# Pi-LPF.net
KiCad netlist of a schematic drawn in EAGLE
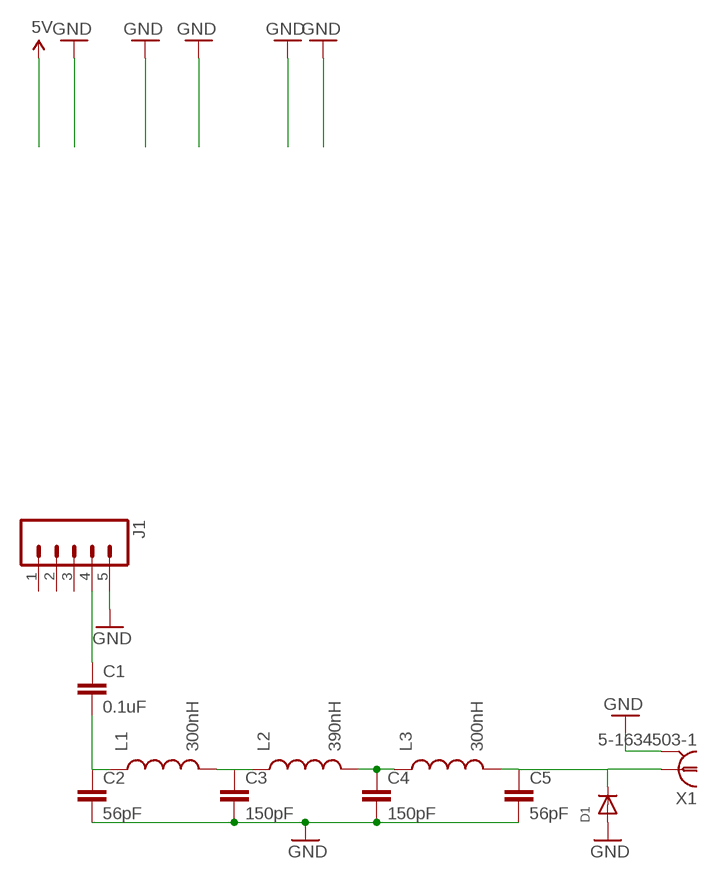
[diagram p0: schematic, sheet 1]

(export (version "E")
  (design (tool "Eeschema 10.0.6"))
  (components
    (comp (ref "C1")
      (value "0.1uF")
      (footprint "eagle-import:1206")
      (fields (field (name "MPN") "12061C104JAT2A"))
      (libsource (lib "eagle-import") (part "CAP1206"))
    )
    (comp (ref "C2")
      (value "56pF")
      (footprint "eagle-import:1206")
      (fields (field (name "MPN") "12061A560JAT2A"))
      (libsource (lib "eagle-import") (part "CAP1206"))
    )
    (comp (ref "C3")
      (value "150pF")
      (footprint "eagle-import:1206")
      (fields (field (name "MPN") "12062A151JAT2A"))
      (libsource (lib "eagle-import") (part "CAP1206"))
    )
    (comp (ref "C4")
      (value "150pF")
      (footprint "eagle-import:1206")
      (fields (field (name "MPN") "12062A151JAT2A"))
      (libsource (lib "eagle-import") (part "CAP1206"))
    )
    (comp (ref "C5")
      (value "56pF")
      (footprint "eagle-import:1206")
      (fields (field (name "MPN") "12061A560JAT2A"))
      (libsource (lib "eagle-import") (part "CAP1206"))
    )
    (comp (ref "D1")
      (value "250mA/100V")
      (footprint "eagle-import:SOD-523")
      (fields (field (name "MPN") "ESD8351XV2T1G"))
      (libsource (lib "eagle-import") (part "DIODESOD-523"))
    )
    (comp (ref "J1")
      (value "M05PTH")
      (footprint "eagle-import:1X05")
      (libsource (lib "eagle-import") (part "M05PTH"))
    )
    (comp (ref "L1")
      (value "300nH")
      (footprint "eagle-import:0603")
      (fields (field (name "MPN") "0603HP-R30X_LU"))
      (libsource (lib "eagle-import") (part "INDUCTOR0603"))
    )
    (comp (ref "L2")
      (value "390nH")
      (footprint "eagle-import:INDUCTOR-1206")
      (fields (field (name "MPN") "1206CS-391XGLB"))
      (libsource (lib "eagle-import") (part "INDUCTORH1206"))
    )
    (comp (ref "L3")
      (value "300nH")
      (footprint "eagle-import:0603")
      (fields (field (name "MPN") "0603HP-R30X_LU"))
      (libsource (lib "eagle-import") (part "INDUCTOR0603"))
    )
    (comp (ref "X1")
      (value "5-1634503-1")
      (footprint "eagle-import:B35N61")
      (fields (field (name "MF") "TE Connectivity"))
      (libsource (lib "eagle-import") (part "BN35N61"))
    )
  )
  (nets
    (net (code "2") (name "GND") (class "Default")
      (node (ref "C2") (pin "2") (pinfunction "2_2") (pintype "passive"))
      (node (ref "C3") (pin "2") (pinfunction "2_2") (pintype "passive"))
      (node (ref "C4") (pin "2") (pinfunction "2_2") (pintype "passive"))
      (node (ref "C5") (pin "2") (pinfunction "2_2") (pintype "passive"))
      (node (ref "D1") (pin "A") (pinfunction "A_A") (pintype "passive"))
      (node (ref "J1") (pin "5") (pinfunction "5_5") (pintype "passive"))
      (node (ref "X1") (pin "2") (pinfunction "2_2") (pintype "passive"))
      (node (ref "X1") (pin "3") (pinfunction "2_3") (pintype "passive"))
      (node (ref "X1") (pin "4") (pinfunction "2_4") (pintype "passive"))
      (node (ref "X1") (pin "5") (pinfunction "2_5") (pintype "passive"))
    )
    (net (code "3") (name "Net-(C1-Pad1)") (class "Default")
      (node (ref "C1") (pin "1") (pinfunction "1_1") (pintype "passive"))
      (node (ref "J1") (pin "4") (pinfunction "4_4") (pintype "passive"))
    )
    (net (code "4") (name "Net-(C1-Pad2)") (class "Default")
      (node (ref "C1") (pin "2") (pinfunction "2_2") (pintype "passive"))
      (node (ref "C2") (pin "1") (pinfunction "1_1") (pintype "passive"))
      (node (ref "L1") (pin "1") (pinfunction "1_1") (pintype "passive"))
    )
    (net (code "5") (name "Net-(D1-C)") (class "Default")
      (node (ref "C5") (pin "1") (pinfunction "1_1") (pintype "passive"))
      (node (ref "D1") (pin "K") (pinfunction "C_K") (pintype "passive"))
      (node (ref "L3") (pin "2") (pinfunction "2_2") (pintype "passive"))
      (node (ref "X1") (pin "1") (pinfunction "1_1") (pintype "passive"))
    )
    (net (code "6") (name "Net-(L2-1)") (class "Default")
      (node (ref "C3") (pin "1") (pinfunction "1_1") (pintype "passive"))
      (node (ref "L1") (pin "2") (pinfunction "2_2") (pintype "passive"))
      (node (ref "L2") (pin "P$1") (pinfunction "1_P$1") (pintype "passive"))
    )
    (net (code "7") (name "Net-(L2-2)") (class "Default")
      (node (ref "C4") (pin "1") (pinfunction "1_1") (pintype "passive"))
      (node (ref "L2") (pin "P$2") (pinfunction "2_P$2") (pintype "passive"))
      (node (ref "L3") (pin "1") (pinfunction "1_1") (pintype "passive"))
    )
    (net (code "8") (name "unconnected-(J1-Pad1)") (class "Default")
      (node (ref "J1") (pin "1") (pinfunction "1_1") (pintype "passive"))
    )
    (net (code "9") (name "unconnected-(J1-Pad2)") (class "Default")
      (node (ref "J1") (pin "2") (pinfunction "2_2") (pintype "passive"))
    )
    (net (code "10") (name "unconnected-(J1-Pad3)") (class "Default")
      (node (ref "J1") (pin "3") (pinfunction "3_3") (pintype "passive"))
    )
  )
)
